# MCU.net
KiCad netlist of a schematic drawn in Altium Designer
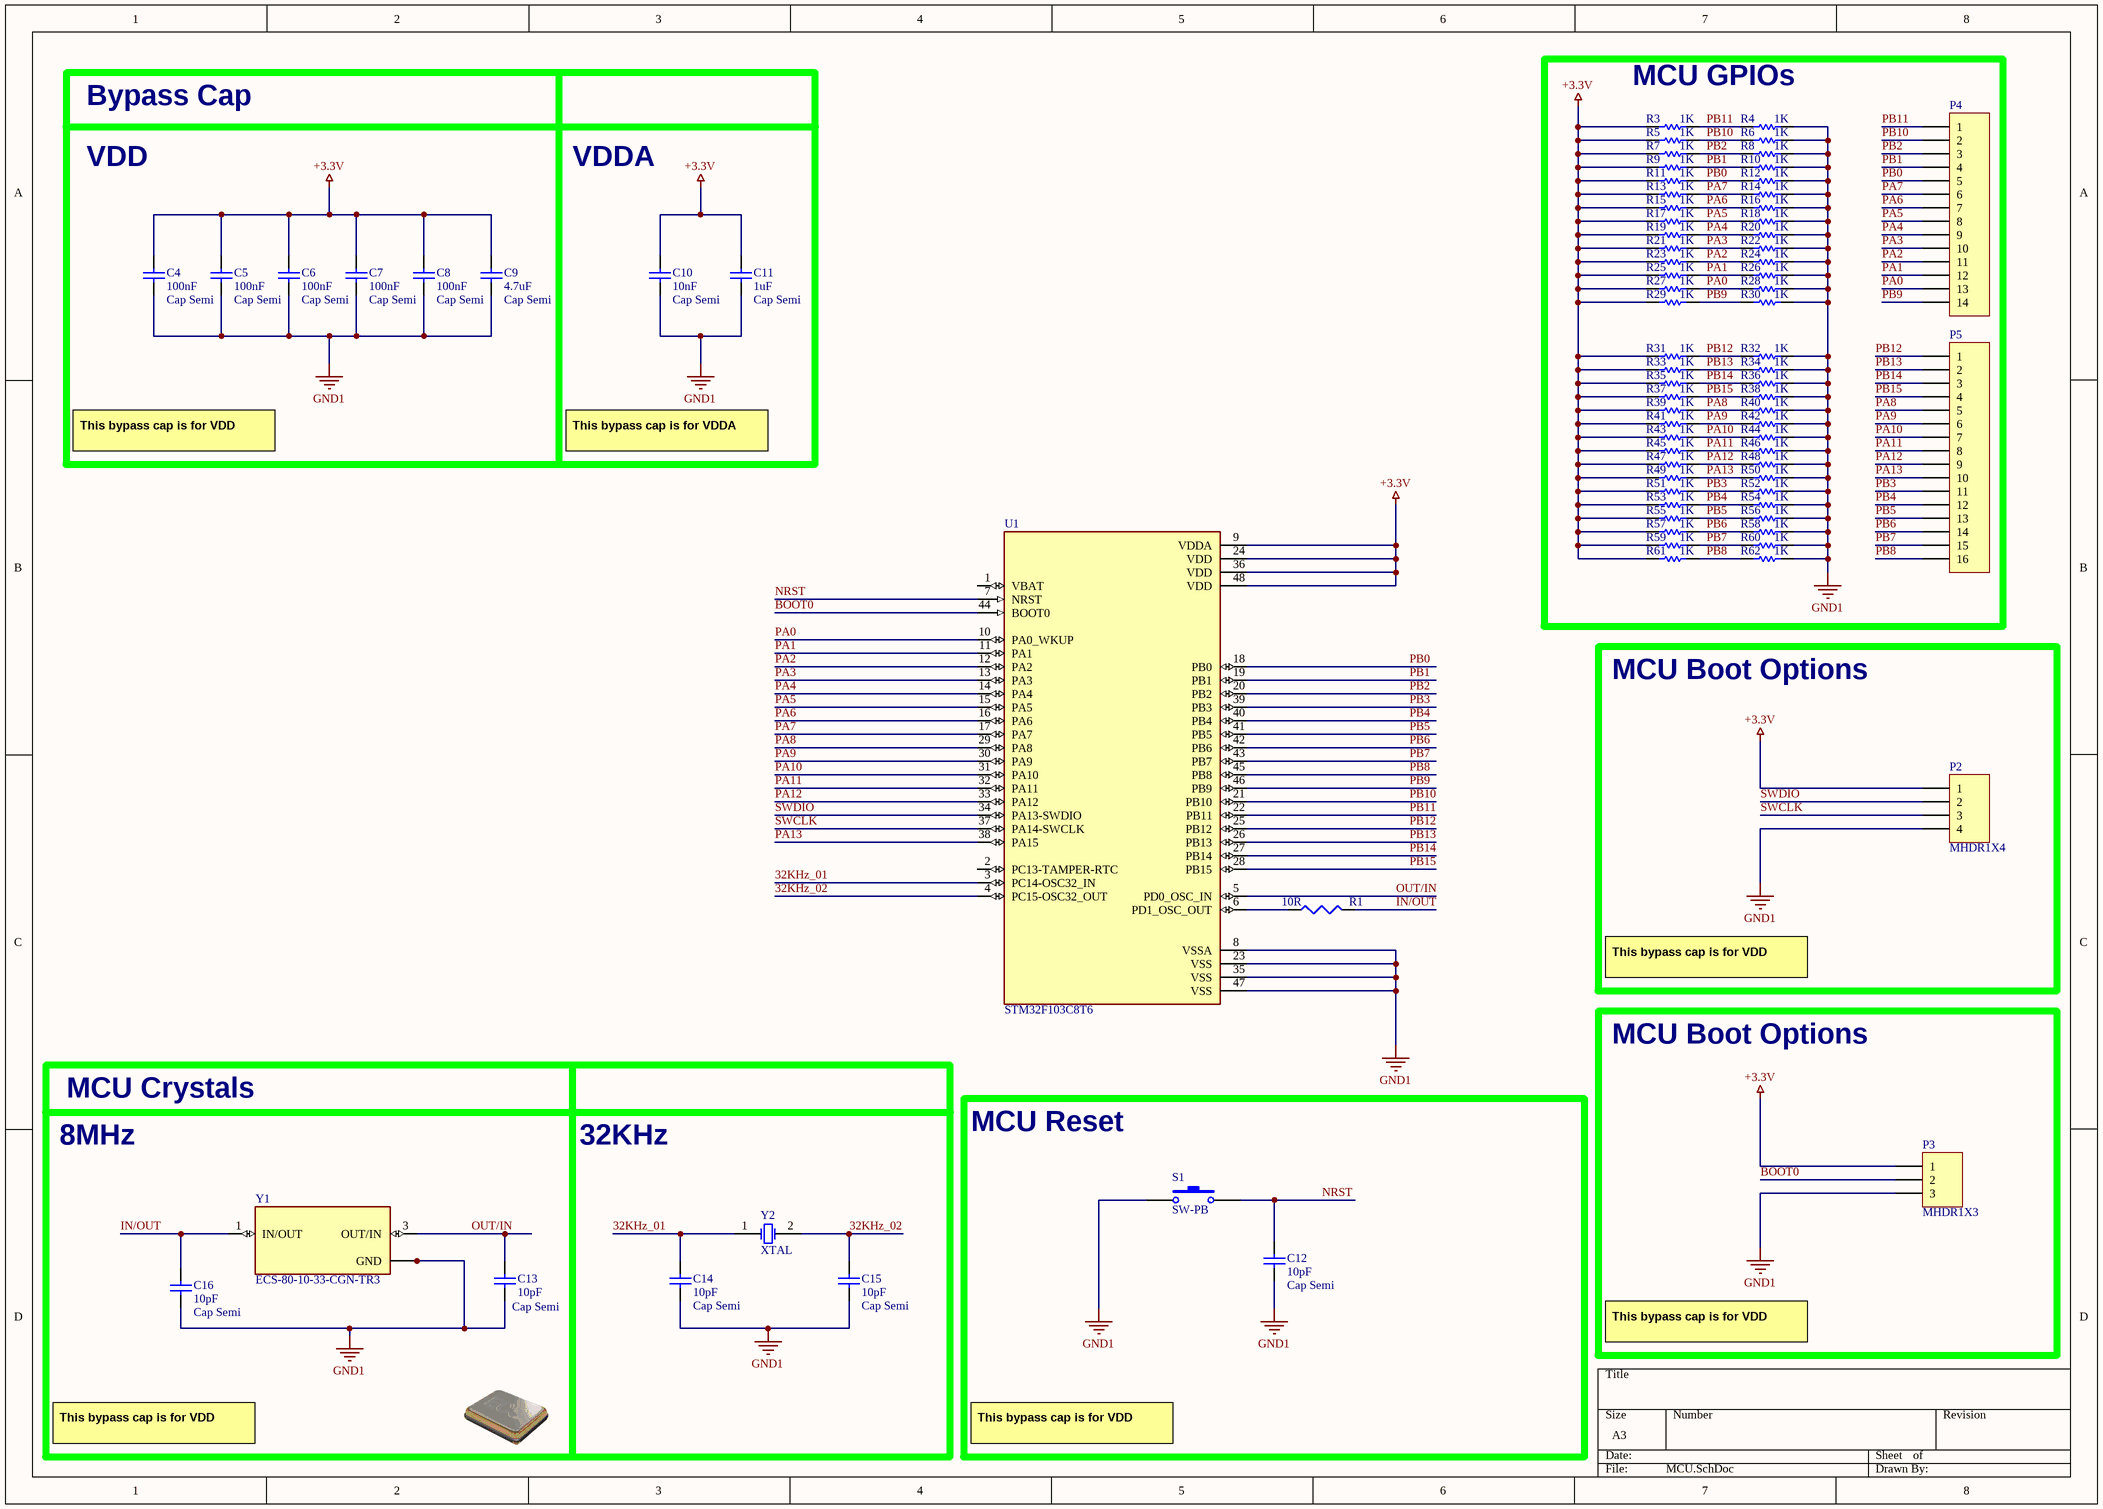
[diagram p0: MCU.SchDoc]

(export (version "E")
  (design (tool "Eeschema 10.0.6"))
  (components
    (comp (ref "C4")
      (value "Cap Semi")
      (footprint "1608[0603]")
      (description "Capacitor (Semiconductor SIM Model)")
      (fields (field (name "ALTIUM_VALUE") "100nF") (field (name "PUBLISHER") "Altium Limited"))
      (libsource (lib "Miscellaneous Devices") (part "Cap Semi"))
    )
    (comp (ref "C5")
      (value "Cap Semi")
      (footprint "1608[0603]")
      (description "Capacitor (Semiconductor SIM Model)")
      (fields (field (name "ALTIUM_VALUE") "100nF") (field (name "PUBLISHER") "Altium Limited"))
      (libsource (lib "Miscellaneous Devices") (part "Cap Semi"))
    )
    (comp (ref "C6")
      (value "Cap Semi")
      (footprint "1608[0603]")
      (description "Capacitor (Semiconductor SIM Model)")
      (fields (field (name "ALTIUM_VALUE") "100nF") (field (name "PUBLISHER") "Altium Limited"))
      (libsource (lib "Miscellaneous Devices") (part "Cap Semi"))
    )
    (comp (ref "C7")
      (value "Cap Semi")
      (footprint "1608[0603]")
      (description "Capacitor (Semiconductor SIM Model)")
      (fields (field (name "ALTIUM_VALUE") "100nF") (field (name "PUBLISHER") "Altium Limited"))
      (libsource (lib "Miscellaneous Devices") (part "Cap Semi"))
    )
    (comp (ref "C8")
      (value "Cap Semi")
      (footprint "1608[0603]")
      (description "Capacitor (Semiconductor SIM Model)")
      (fields (field (name "ALTIUM_VALUE") "100nF") (field (name "PUBLISHER") "Altium Limited"))
      (libsource (lib "Miscellaneous Devices") (part "Cap Semi"))
    )
    (comp (ref "C9")
      (value "Cap Semi")
      (footprint "1608[0603]")
      (description "Capacitor (Semiconductor SIM Model)")
      (fields (field (name "ALTIUM_VALUE") "4.7uF") (field (name "PUBLISHER") "Altium Limited"))
      (libsource (lib "Miscellaneous Devices") (part "Cap Semi"))
    )
    (comp (ref "C10")
      (value "Cap Semi")
      (footprint "1608[0603]")
      (description "Capacitor (Semiconductor SIM Model)")
      (fields (field (name "ALTIUM_VALUE") "10nF") (field (name "PUBLISHER") "Altium Limited"))
      (libsource (lib "Miscellaneous Devices") (part "Cap Semi"))
    )
    (comp (ref "C11")
      (value "Cap Semi")
      (footprint "1608[0603]")
      (description "Capacitor (Semiconductor SIM Model)")
      (fields (field (name "ALTIUM_VALUE") "1uF") (field (name "PUBLISHER") "Altium Limited"))
      (libsource (lib "Miscellaneous Devices") (part "Cap Semi"))
    )
    (comp (ref "C12")
      (value "Cap Semi")
      (footprint "0402")
      (description "Capacitor (Semiconductor SIM Model)")
      (fields (field (name "ALTIUM_VALUE") "10pF") (field (name "PUBLISHER") "Altium Limited"))
      (libsource (lib "Miscellaneous Devices") (part "Cap Semi"))
    )
    (comp (ref "C13")
      (value "Cap Semi")
      (footprint "0402")
      (description "Capacitor (Semiconductor SIM Model)")
      (fields (field (name "ALTIUM_VALUE") "10pF") (field (name "PUBLISHER") "Altium Limited"))
      (libsource (lib "Miscellaneous Devices") (part "Cap Semi"))
    )
    (comp (ref "C14")
      (value "Cap Semi")
      (footprint "0402")
      (description "Capacitor (Semiconductor SIM Model)")
      (fields (field (name "ALTIUM_VALUE") "10pF") (field (name "PUBLISHER") "Altium Limited"))
      (libsource (lib "Miscellaneous Devices") (part "Cap Semi"))
    )
    (comp (ref "C15")
      (value "Cap Semi")
      (footprint "0402")
      (description "Capacitor (Semiconductor SIM Model)")
      (fields (field (name "ALTIUM_VALUE") "10pF") (field (name "PUBLISHER") "Altium Limited"))
      (libsource (lib "Miscellaneous Devices") (part "Cap Semi"))
    )
    (comp (ref "C16")
      (value "Cap Semi")
      (footprint "0402")
      (description "Capacitor (Semiconductor SIM Model)")
      (fields (field (name "ALTIUM_VALUE") "10pF") (field (name "PUBLISHER") "Altium Limited"))
      (libsource (lib "Miscellaneous Devices") (part "Cap Semi"))
    )
    (comp (ref "P2")
      (value "MHDR1X4")
      (footprint "MHDR1X4")
      (description "Header, 4-Pin")
      (fields (field (name "PUBLISHER") "Altium Limited"))
      (libsource (lib "Miscellaneous Connectors") (part "MHDR1X4"))
    )
    (comp (ref "P3")
      (value "MHDR1X3")
      (footprint "MHDR1X3")
      (description "Header, 3-Pin")
      (fields (field (name "PUBLISHER") "Altium Limited"))
      (libsource (lib "Miscellaneous Connectors") (part "MHDR1X3"))
    )
    (comp (ref "P4")
      (value "Header 14")
      (footprint "MY_FE14")
      (description "Header, 14-Pin")
      (fields (field (name "ASID PART NUMBER") "Header 14-AS"))
      (libsource (lib "003 Mylib-Rev-4") (part "Header 14"))
    )
    (comp (ref "P5")
      (value "Header 16")
      (footprint "MY_FE16")
      (description "Header, 16-Pin")
      (fields (field (name "ASID PART NUMBER") "Header 16-AS"))
      (libsource (lib "003 Mylib-Rev-4") (part "Header 16"))
    )
    (comp (ref "R1")
      (value "10R")
      (footprint "J1-0603")
      (description "Resistor")
      (fields (field (name "Comment") "Res3") (field (name "PUBLISHER") "Altium Limited"))
      (libsource (lib "Miscellaneous Devices") (part "Res3"))
    )
    (comp (ref "R3")
      (value "1K")
      (footprint "MY_0603")
      (description "Standard resistor")
      (fields (field (name "ASID PART NUMBER") "Res-AS"))
      (libsource (lib "003 Mylib-Rev-4") (part "Res"))
    )
    (comp (ref "R4")
      (value "1K")
      (footprint "MY_0603")
      (description "Standard resistor")
      (fields (field (name "ASID PART NUMBER") "Res-AS"))
      (libsource (lib "003 Mylib-Rev-4") (part "Res"))
    )
    (comp (ref "R5")
      (value "1K")
      (footprint "MY_0603")
      (description "Standard resistor")
      (fields (field (name "ASID PART NUMBER") "Res-AS"))
      (libsource (lib "003 Mylib-Rev-4") (part "Res"))
    )
    (comp (ref "R6")
      (value "1K")
      (footprint "MY_0603")
      (description "Standard resistor")
      (fields (field (name "ASID PART NUMBER") "Res-AS"))
      (libsource (lib "003 Mylib-Rev-4") (part "Res"))
    )
    (comp (ref "R7")
      (value "1K")
      (footprint "MY_0603")
      (description "Standard resistor")
      (fields (field (name "ASID PART NUMBER") "Res-AS"))
      (libsource (lib "003 Mylib-Rev-4") (part "Res"))
    )
    (comp (ref "R8")
      (value "1K")
      (footprint "MY_0603")
      (description "Standard resistor")
      (fields (field (name "ASID PART NUMBER") "Res-AS"))
      (libsource (lib "003 Mylib-Rev-4") (part "Res"))
    )
    (comp (ref "R9")
      (value "1K")
      (footprint "MY_0603")
      (description "Standard resistor")
      (fields (field (name "ASID PART NUMBER") "Res-AS"))
      (libsource (lib "003 Mylib-Rev-4") (part "Res"))
    )
    (comp (ref "R10")
      (value "1K")
      (footprint "MY_0603")
      (description "Standard resistor")
      (fields (field (name "ASID PART NUMBER") "Res-AS"))
      (libsource (lib "003 Mylib-Rev-4") (part "Res"))
    )
    (comp (ref "R11")
      (value "1K")
      (footprint "MY_0603")
      (description "Standard resistor")
      (fields (field (name "ASID PART NUMBER") "Res-AS"))
      (libsource (lib "003 Mylib-Rev-4") (part "Res"))
    )
    (comp (ref "R12")
      (value "1K")
      (footprint "MY_0603")
      (description "Standard resistor")
      (fields (field (name "ASID PART NUMBER") "Res-AS"))
      (libsource (lib "003 Mylib-Rev-4") (part "Res"))
    )
    (comp (ref "R13")
      (value "1K")
      (footprint "MY_0603")
      (description "Standard resistor")
      (fields (field (name "ASID PART NUMBER") "Res-AS"))
      (libsource (lib "003 Mylib-Rev-4") (part "Res"))
    )
    (comp (ref "R14")
      (value "1K")
      (footprint "MY_0603")
      (description "Standard resistor")
      (fields (field (name "ASID PART NUMBER") "Res-AS"))
      (libsource (lib "003 Mylib-Rev-4") (part "Res"))
    )
    (comp (ref "R15")
      (value "1K")
      (footprint "MY_0603")
      (description "Standard resistor")
      (fields (field (name "ASID PART NUMBER") "Res-AS"))
      (libsource (lib "003 Mylib-Rev-4") (part "Res"))
    )
    (comp (ref "R16")
      (value "1K")
      (footprint "MY_0603")
      (description "Standard resistor")
      (fields (field (name "ASID PART NUMBER") "Res-AS"))
      (libsource (lib "003 Mylib-Rev-4") (part "Res"))
    )
    (comp (ref "R17")
      (value "1K")
      (footprint "MY_0603")
      (description "Standard resistor")
      (fields (field (name "ASID PART NUMBER") "Res-AS"))
      (libsource (lib "003 Mylib-Rev-4") (part "Res"))
    )
    (comp (ref "R18")
      (value "1K")
      (footprint "MY_0603")
      (description "Standard resistor")
      (fields (field (name "ASID PART NUMBER") "Res-AS"))
      (libsource (lib "003 Mylib-Rev-4") (part "Res"))
    )
    (comp (ref "R19")
      (value "1K")
      (footprint "MY_0603")
      (description "Standard resistor")
      (fields (field (name "ASID PART NUMBER") "Res-AS"))
      (libsource (lib "003 Mylib-Rev-4") (part "Res"))
    )
    (comp (ref "R20")
      (value "1K")
      (footprint "MY_0603")
      (description "Standard resistor")
      (fields (field (name "ASID PART NUMBER") "Res-AS"))
      (libsource (lib "003 Mylib-Rev-4") (part "Res"))
    )
    (comp (ref "R21")
      (value "1K")
      (footprint "MY_0603")
      (description "Standard resistor")
      (fields (field (name "ASID PART NUMBER") "Res-AS"))
      (libsource (lib "003 Mylib-Rev-4") (part "Res"))
    )
    (comp (ref "R22")
      (value "1K")
      (footprint "MY_0603")
      (description "Standard resistor")
      (fields (field (name "ASID PART NUMBER") "Res-AS"))
      (libsource (lib "003 Mylib-Rev-4") (part "Res"))
    )
    (comp (ref "R23")
      (value "1K")
      (footprint "MY_0603")
      (description "Standard resistor")
      (fields (field (name "ASID PART NUMBER") "Res-AS"))
      (libsource (lib "003 Mylib-Rev-4") (part "Res"))
    )
    (comp (ref "R24")
      (value "1K")
      (footprint "MY_0603")
      (description "Standard resistor")
      (fields (field (name "ASID PART NUMBER") "Res-AS"))
      (libsource (lib "003 Mylib-Rev-4") (part "Res"))
    )
    (comp (ref "R25")
      (value "1K")
      (footprint "MY_0603")
      (description "Standard resistor")
      (fields (field (name "ASID PART NUMBER") "Res-AS"))
      (libsource (lib "003 Mylib-Rev-4") (part "Res"))
    )
    (comp (ref "R26")
      (value "1K")
      (footprint "MY_0603")
      (description "Standard resistor")
      (fields (field (name "ASID PART NUMBER") "Res-AS"))
      (libsource (lib "003 Mylib-Rev-4") (part "Res"))
    )
    (comp (ref "R27")
      (value "1K")
      (footprint "MY_0603")
      (description "Standard resistor")
      (fields (field (name "ASID PART NUMBER") "Res-AS"))
      (libsource (lib "003 Mylib-Rev-4") (part "Res"))
    )
    (comp (ref "R28")
      (value "1K")
      (footprint "MY_0603")
      (description "Standard resistor")
      (fields (field (name "ASID PART NUMBER") "Res-AS"))
      (libsource (lib "003 Mylib-Rev-4") (part "Res"))
    )
    (comp (ref "R29")
      (value "1K")
      (footprint "MY_0603")
      (description "Standard resistor")
      (fields (field (name "ASID PART NUMBER") "Res-AS"))
      (libsource (lib "003 Mylib-Rev-4") (part "Res"))
    )
    (comp (ref "R30")
      (value "1K")
      (footprint "MY_0603")
      (description "Standard resistor")
      (fields (field (name "ASID PART NUMBER") "Res-AS"))
      (libsource (lib "003 Mylib-Rev-4") (part "Res"))
    )
    (comp (ref "R31")
      (value "1K")
      (footprint "MY_0603")
      (description "Standard resistor")
      (fields (field (name "ASID PART NUMBER") "Res-AS"))
      (libsource (lib "003 Mylib-Rev-4") (part "Res"))
    )
    (comp (ref "R32")
      (value "1K")
      (footprint "MY_0603")
      (description "Standard resistor")
      (fields (field (name "ASID PART NUMBER") "Res-AS"))
      (libsource (lib "003 Mylib-Rev-4") (part "Res"))
    )
    (comp (ref "R33")
      (value "1K")
      (footprint "MY_0603")
      (description "Standard resistor")
      (fields (field (name "ASID PART NUMBER") "Res-AS"))
      (libsource (lib "003 Mylib-Rev-4") (part "Res"))
    )
    (comp (ref "R34")
      (value "1K")
      (footprint "MY_0603")
      (description "Standard resistor")
      (fields (field (name "ASID PART NUMBER") "Res-AS"))
      (libsource (lib "003 Mylib-Rev-4") (part "Res"))
    )
    (comp (ref "R35")
      (value "1K")
      (footprint "MY_0603")
      (description "Standard resistor")
      (fields (field (name "ASID PART NUMBER") "Res-AS"))
      (libsource (lib "003 Mylib-Rev-4") (part "Res"))
    )
    (comp (ref "R36")
      (value "1K")
      (footprint "MY_0603")
      (description "Standard resistor")
      (fields (field (name "ASID PART NUMBER") "Res-AS"))
      (libsource (lib "003 Mylib-Rev-4") (part "Res"))
    )
    (comp (ref "R37")
      (value "1K")
      (footprint "MY_0603")
      (description "Standard resistor")
      (fields (field (name "ASID PART NUMBER") "Res-AS"))
      (libsource (lib "003 Mylib-Rev-4") (part "Res"))
    )
    (comp (ref "R38")
      (value "1K")
      (footprint "MY_0603")
      (description "Standard resistor")
      (fields (field (name "ASID PART NUMBER") "Res-AS"))
      (libsource (lib "003 Mylib-Rev-4") (part "Res"))
    )
    (comp (ref "R39")
      (value "1K")
      (footprint "MY_0603")
      (description "Standard resistor")
      (fields (field (name "ASID PART NUMBER") "Res-AS"))
      (libsource (lib "003 Mylib-Rev-4") (part "Res"))
    )
    (comp (ref "R40")
      (value "1K")
      (footprint "MY_0603")
      (description "Standard resistor")
      (fields (field (name "ASID PART NUMBER") "Res-AS"))
      (libsource (lib "003 Mylib-Rev-4") (part "Res"))
    )
    (comp (ref "R41")
      (value "1K")
      (footprint "MY_0603")
      (description "Standard resistor")
      (fields (field (name "ASID PART NUMBER") "Res-AS"))
      (libsource (lib "003 Mylib-Rev-4") (part "Res"))
    )
    (comp (ref "R42")
      (value "1K")
      (footprint "MY_0603")
      (description "Standard resistor")
      (fields (field (name "ASID PART NUMBER") "Res-AS"))
      (libsource (lib "003 Mylib-Rev-4") (part "Res"))
    )
    (comp (ref "R43")
      (value "1K")
      (footprint "MY_0603")
      (description "Standard resistor")
      (fields (field (name "ASID PART NUMBER") "Res-AS"))
      (libsource (lib "003 Mylib-Rev-4") (part "Res"))
    )
    (comp (ref "R44")
      (value "1K")
      (footprint "MY_0603")
      (description "Standard resistor")
      (fields (field (name "ASID PART NUMBER") "Res-AS"))
      (libsource (lib "003 Mylib-Rev-4") (part "Res"))
    )
    (comp (ref "R45")
      (value "1K")
      (footprint "MY_0603")
      (description "Standard resistor")
      (fields (field (name "ASID PART NUMBER") "Res-AS"))
      (libsource (lib "003 Mylib-Rev-4") (part "Res"))
    )
    (comp (ref "R46")
      (value "1K")
      (footprint "MY_0603")
      (description "Standard resistor")
      (fields (field (name "ASID PART NUMBER") "Res-AS"))
      (libsource (lib "003 Mylib-Rev-4") (part "Res"))
    )
    (comp (ref "R47")
      (value "1K")
      (footprint "MY_0603")
      (description "Standard resistor")
      (fields (field (name "ASID PART NUMBER") "Res-AS"))
      (libsource (lib "003 Mylib-Rev-4") (part "Res"))
    )
    (comp (ref "R48")
      (value "1K")
      (footprint "MY_0603")
      (description "Standard resistor")
      (fields (field (name "ASID PART NUMBER") "Res-AS"))
      (libsource (lib "003 Mylib-Rev-4") (part "Res"))
    )
    (comp (ref "R49")
      (value "1K")
      (footprint "MY_0603")
      (description "Standard resistor")
      (fields (field (name "ASID PART NUMBER") "Res-AS"))
      (libsource (lib "003 Mylib-Rev-4") (part "Res"))
    )
    (comp (ref "R50")
      (value "1K")
      (footprint "MY_0603")
      (description "Standard resistor")
      (fields (field (name "ASID PART NUMBER") "Res-AS"))
      (libsource (lib "003 Mylib-Rev-4") (part "Res"))
    )
    (comp (ref "R51")
      (value "1K")
      (footprint "MY_0603")
      (description "Standard resistor")
      (fields (field (name "ASID PART NUMBER") "Res-AS"))
      (libsource (lib "003 Mylib-Rev-4") (part "Res"))
    )
    (comp (ref "R52")
      (value "1K")
      (footprint "MY_0603")
      (description "Standard resistor")
      (fields (field (name "ASID PART NUMBER") "Res-AS"))
      (libsource (lib "003 Mylib-Rev-4") (part "Res"))
    )
    (comp (ref "R53")
      (value "1K")
      (footprint "MY_0603")
      (description "Standard resistor")
      (fields (field (name "ASID PART NUMBER") "Res-AS"))
      (libsource (lib "003 Mylib-Rev-4") (part "Res"))
    )
    (comp (ref "R54")
      (value "1K")
      (footprint "MY_0603")
      (description "Standard resistor")
      (fields (field (name "ASID PART NUMBER") "Res-AS"))
      (libsource (lib "003 Mylib-Rev-4") (part "Res"))
    )
    (comp (ref "R55")
      (value "1K")
      (footprint "MY_0603")
      (description "Standard resistor")
      (fields (field (name "ASID PART NUMBER") "Res-AS"))
      (libsource (lib "003 Mylib-Rev-4") (part "Res"))
    )
    (comp (ref "R56")
      (value "1K")
      (footprint "MY_0603")
      (description "Standard resistor")
      (fields (field (name "ASID PART NUMBER") "Res-AS"))
      (libsource (lib "003 Mylib-Rev-4") (part "Res"))
    )
    (comp (ref "R57")
      (value "1K")
      (footprint "MY_0603")
      (description "Standard resistor")
      (fields (field (name "ASID PART NUMBER") "Res-AS"))
      (libsource (lib "003 Mylib-Rev-4") (part "Res"))
    )
    (comp (ref "R58")
      (value "1K")
      (footprint "MY_0603")
      (description "Standard resistor")
      (fields (field (name "ASID PART NUMBER") "Res-AS"))
      (libsource (lib "003 Mylib-Rev-4") (part "Res"))
    )
    (comp (ref "R59")
      (value "1K")
      (footprint "MY_0603")
      (description "Standard resistor")
      (fields (field (name "ASID PART NUMBER") "Res-AS"))
      (libsource (lib "003 Mylib-Rev-4") (part "Res"))
    )
    (comp (ref "R60")
      (value "1K")
      (footprint "MY_0603")
      (description "Standard resistor")
      (fields (field (name "ASID PART NUMBER") "Res-AS"))
      (libsource (lib "003 Mylib-Rev-4") (part "Res"))
    )
    (comp (ref "R61")
      (value "1K")
      (footprint "MY_0603")
      (description "Standard resistor")
      (fields (field (name "ASID PART NUMBER") "Res-AS"))
      (libsource (lib "003 Mylib-Rev-4") (part "Res"))
    )
    (comp (ref "R62")
      (value "1K")
      (footprint "MY_0603")
      (description "Standard resistor")
      (fields (field (name "ASID PART NUMBER") "Res-AS"))
      (libsource (lib "003 Mylib-Rev-4") (part "Res"))
    )
    (comp (ref "S1")
      (value "SW-PB")
      (footprint "SPST-2")
      (description "Switch")
      (fields (field (name "PUBLISHER") "Altium Limited"))
      (libsource (lib "Miscellaneous Devices") (part "SW-PB"))
    )
    (comp (ref "U1")
      (value "STM32F103C8T6")
      (footprint "QFP50P900X900X160-48N")
      (description "ARM® Cortex®-M3 STM32F1 Microcontroller IC 32-Bit 72MHz 64KB (64K x 8) FLASH 48-LQFP (7x7)")
      (fields (field (name "MF") "STMicroelectronics"))
      (libsource (lib "STM32F103C8T6") (part "STM32F103C8T6"))
    )
    (comp (ref "Y1")
      (value "ECS-80-10-33-CGN-TR3")
      (footprint "XTAL_ECS-80-10-33-CGN-TR3")
      (libsource (lib "ECS-80-10-33-CGN-TR3") (part "ECS-80-10-33-CGN-TR3"))
    )
    (comp (ref "Y2")
      (value "XTAL")
      (footprint "R38")
      (description "Crystal Oscillator")
      (fields (field (name "PUBLISHER") "Altium Limited"))
      (libsource (lib "Miscellaneous Devices") (part "XTAL"))
    )
  )
  (nets
    (net (code "1") (name "+3.3V") (class "Default")
      (node (ref "C10") (pin "2") (pinfunction "2_2") (pintype "passive"))
      (node (ref "C11") (pin "2") (pinfunction "2_2") (pintype "passive"))
      (node (ref "C4") (pin "2") (pinfunction "2_2") (pintype "passive"))
      (node (ref "C5") (pin "2") (pinfunction "2_2") (pintype "passive"))
      (node (ref "C6") (pin "2") (pinfunction "2_2") (pintype "passive"))
      (node (ref "C7") (pin "2") (pinfunction "2_2") (pintype "passive"))
      (node (ref "C8") (pin "2") (pinfunction "2_2") (pintype "passive"))
      (node (ref "C9") (pin "2") (pinfunction "2_2") (pintype "passive"))
      (node (ref "P2") (pin "1") (pinfunction "1_1") (pintype "passive"))
      (node (ref "P3") (pin "1") (pinfunction "1_1") (pintype "passive"))
      (node (ref "R11") (pin "1") (pinfunction "1_1") (pintype "passive"))
      (node (ref "R13") (pin "1") (pinfunction "1_1") (pintype "passive"))
      (node (ref "R15") (pin "1") (pinfunction "1_1") (pintype "passive"))
      (node (ref "R17") (pin "1") (pinfunction "1_1") (pintype "passive"))
      (node (ref "R19") (pin "1") (pinfunction "1_1") (pintype "passive"))
      (node (ref "R21") (pin "1") (pinfunction "1_1") (pintype "passive"))
      (node (ref "R23") (pin "1") (pinfunction "1_1") (pintype "passive"))
      (node (ref "R25") (pin "1") (pinfunction "1_1") (pintype "passive"))
      (node (ref "R27") (pin "1") (pinfunction "1_1") (pintype "passive"))
      (node (ref "R29") (pin "1") (pinfunction "1_1") (pintype "passive"))
      (node (ref "R3") (pin "1") (pinfunction "1_1") (pintype "passive"))
      (node (ref "R31") (pin "1") (pinfunction "1_1") (pintype "passive"))
      (node (ref "R33") (pin "1") (pinfunction "1_1") (pintype "passive"))
      (node (ref "R35") (pin "1") (pinfunction "1_1") (pintype "passive"))
      (node (ref "R37") (pin "1") (pinfunction "1_1") (pintype "passive"))
      (node (ref "R39") (pin "1") (pinfunction "1_1") (pintype "passive"))
      (node (ref "R41") (pin "1") (pinfunction "1_1") (pintype "passive"))
      (node (ref "R43") (pin "1") (pinfunction "1_1") (pintype "passive"))
      (node (ref "R45") (pin "1") (pinfunction "1_1") (pintype "passive"))
      (node (ref "R47") (pin "1") (pinfunction "1_1") (pintype "passive"))
      (node (ref "R49") (pin "1") (pinfunction "1_1") (pintype "passive"))
      (node (ref "R5") (pin "1") (pinfunction "1_1") (pintype "passive"))
      (node (ref "R51") (pin "1") (pinfunction "1_1") (pintype "passive"))
      (node (ref "R53") (pin "1") (pinfunction "1_1") (pintype "passive"))
      (node (ref "R55") (pin "1") (pinfunction "1_1") (pintype "passive"))
      (node (ref "R57") (pin "1") (pinfunction "1_1") (pintype "passive"))
      (node (ref "R59") (pin "1") (pinfunction "1_1") (pintype "passive"))
      (node (ref "R61") (pin "1") (pinfunction "1_1") (pintype "passive"))
      (node (ref "R7") (pin "1") (pinfunction "1_1") (pintype "passive"))
      (node (ref "R9") (pin "1") (pinfunction "1_1") (pintype "passive"))
      (node (ref "U1") (pin "24") (pinfunction "VDD_24") (pintype "power_in"))
      (node (ref "U1") (pin "36") (pinfunction "VDD_36") (pintype "power_in"))
      (node (ref "U1") (pin "48") (pinfunction "VDD_48") (pintype "power_in"))
      (node (ref "U1") (pin "9") (pinfunction "VDDA_9") (pintype "power_in"))
    )
    (net (code "2") (name "/32KHz_01") (class "Default")
      (node (ref "C14") (pin "2") (pinfunction "2_2") (pintype "passive"))
      (node (ref "U1") (pin "3") (pinfunction "PC14-OSC32_IN_3") (pintype "bidirectional"))
      (node (ref "Y2") (pin "1") (pinfunction "OSC1_1") (pintype "passive"))
    )
    (net (code "3") (name "/32KHz_02") (class "Default")
      (node (ref "C15") (pin "2") (pinfunction "2_2") (pintype "passive"))
      (node (ref "U1") (pin "4") (pinfunction "PC15-OSC32_OUT_4") (pintype "bidirectional"))
      (node (ref "Y2") (pin "2") (pinfunction "OSC2_2") (pintype "passive"))
    )
    (net (code "4") (name "/BOOT0") (class "Default")
      (node (ref "P3") (pin "2") (pinfunction "2_2") (pintype "passive"))
      (node (ref "U1") (pin "44") (pinfunction "BOOT0_44") (pintype "input"))
    )
    (net (code "5") (name "/IN{slash}OUT") (class "Default")
      (node (ref "C16") (pin "2") (pinfunction "2_2") (pintype "passive"))
      (node (ref "R1") (pin "2") (pinfunction "2_2") (pintype "passive"))
      (node (ref "Y1") (pin "1") (pinfunction "IN/OUT_1") (pintype "bidirectional"))
    )
    (net (code "6") (name "/NRST") (class "Default")
      (node (ref "C12") (pin "2") (pinfunction "2_2") (pintype "passive"))
      (node (ref "S1") (pin "2") (pinfunction "2_2") (pintype "passive"))
      (node (ref "U1") (pin "7") (pinfunction "NRST_7") (pintype "input"))
    )
    (net (code "7") (name "/OUT{slash}IN") (class "Default")
      (node (ref "C13") (pin "2") (pinfunction "2_2") (pintype "passive"))
      (node (ref "U1") (pin "5") (pinfunction "PD0_OSC_IN_5") (pintype "bidirectional"))
      (node (ref "Y1") (pin "3") (pinfunction "OUT/IN_3") (pintype "bidirectional"))
    )
    (net (code "8") (name "/PA0") (class "Default")
      (node (ref "P4") (pin "13") (pinfunction "13_13") (pintype "passive"))
      (node (ref "R27") (pin "2") (pinfunction "2_2") (pintype "passive"))
      (node (ref "R28") (pin "1") (pinfunction "1_1") (pintype "passive"))
      (node (ref "U1") (pin "10") (pinfunction "PA0_WKUP_10") (pintype "bidirectional"))
    )
    (net (code "9") (name "/PA1") (class "Default")
      (node (ref "P4") (pin "12") (pinfunction "12_12") (pintype "passive"))
      (node (ref "R25") (pin "2") (pinfunction "2_2") (pintype "passive"))
      (node (ref "R26") (pin "1") (pinfunction "1_1") (pintype "passive"))
      (node (ref "U1") (pin "11") (pinfunction "PA1_11") (pintype "bidirectional"))
    )
    (net (code "10") (name "/PA2") (class "Default")
      (node (ref "P4") (pin "11") (pinfunction "11_11") (pintype "passive"))
      (node (ref "R23") (pin "2") (pinfunction "2_2") (pintype "passive"))
      (node (ref "R24") (pin "1") (pinfunction "1_1") (pintype "passive"))
      (node (ref "U1") (pin "12") (pinfunction "PA2_12") (pintype "bidirectional"))
    )
    (net (code "11") (name "/PA3") (class "Default")
      (node (ref "P4") (pin "10") (pinfunction "10_10") (pintype "passive"))
      (node (ref "R21") (pin "2") (pinfunction "2_2") (pintype "passive"))
      (node (ref "R22") (pin "1") (pinfunction "1_1") (pintype "passive"))
      (node (ref "U1") (pin "13") (pinfunction "PA3_13") (pintype "bidirectional"))
    )
    (net (code "12") (name "/PA4") (class "Default")
      (node (ref "P4") (pin "9") (pinfunction "9_9") (pintype "passive"))
      (node (ref "R19") (pin "2") (pinfunction "2_2") (pintype "passive"))
      (node (ref "R20") (pin "1") (pinfunction "1_1") (pintype "passive"))
      (node (ref "U1") (pin "14") (pinfunction "PA4_14") (pintype "bidirectional"))
    )
    (net (code "13") (name "/PA5") (class "Default")
      (node (ref "P4") (pin "8") (pinfunction "8_8") (pintype "passive"))
      (node (ref "R17") (pin "2") (pinfunction "2_2") (pintype "passive"))
      (node (ref "R18") (pin "1") (pinfunction "1_1") (pintype "passive"))
      (node (ref "U1") (pin "15") (pinfunction "PA5_15") (pintype "bidirectional"))
    )
    (net (code "14") (name "/PA6") (class "Default")
      (node (ref "P4") (pin "7") (pinfunction "7_7") (pintype "passive"))
      (node (ref "R15") (pin "2") (pinfunction "2_2") (pintype "passive"))
      (node (ref "R16") (pin "1") (pinfunction "1_1") (pintype "passive"))
      (node (ref "U1") (pin "16") (pinfunction "PA6_16") (pintype "bidirectional"))
    )
    (net (code "15") (name "/PA7") (class "Default")
      (node (ref "P4") (pin "6") (pinfunction "6_6") (pintype "passive"))
      (node (ref "R13") (pin "2") (pinfunction "2_2") (pintype "passive"))
      (node (ref "R14") (pin "1") (pinfunction "1_1") (pintype "passive"))
      (node (ref "U1") (pin "17") (pinfunction "PA7_17") (pintype "bidirectional"))
    )
    (net (code "16") (name "/PA8") (class "Default")
      (node (ref "P5") (pin "5") (pinfunction "5_5") (pintype "passive"))
      (node (ref "R39") (pin "2") (pinfunction "2_2") (pintype "passive"))
      (node (ref "R40") (pin "1") (pinfunction "1_1") (pintype "passive"))
      (node (ref "U1") (pin "29") (pinfunction "PA8_29") (pintype "bidirectional"))
    )
    (net (code "17") (name "/PA9") (class "Default")
      (node (ref "P5") (pin "6") (pinfunction "6_6") (pintype "passive"))
      (node (ref "R41") (pin "2") (pinfunction "2_2") (pintype "passive"))
      (node (ref "R42") (pin "1") (pinfunction "1_1") (pintype "passive"))
      (node (ref "U1") (pin "30") (pinfunction "PA9_30") (pintype "bidirectional"))
    )
    (net (code "18") (name "/PA10") (class "Default")
      (node (ref "P5") (pin "7") (pinfunction "7_7") (pintype "passive"))
      (node (ref "R43") (pin "2") (pinfunction "2_2") (pintype "passive"))
      (node (ref "R44") (pin "1") (pinfunction "1_1") (pintype "passive"))
      (node (ref "U1") (pin "31") (pinfunction "PA10_31") (pintype "bidirectional"))
    )
    (net (code "19") (name "/PA11") (class "Default")
      (node (ref "P5") (pin "8") (pinfunction "8_8") (pintype "passive"))
      (node (ref "R45") (pin "2") (pinfunction "2_2") (pintype "passive"))
      (node (ref "R46") (pin "1") (pinfunction "1_1") (pintype "passive"))
      (node (ref "U1") (pin "32") (pinfunction "PA11_32") (pintype "bidirectional"))
    )
    (net (code "20") (name "/PA12") (class "Default")
      (node (ref "P5") (pin "9") (pinfunction "9_9") (pintype "passive"))
      (node (ref "R47") (pin "2") (pinfunction "2_2") (pintype "passive"))
      (node (ref "R48") (pin "1") (pinfunction "1_1") (pintype "passive"))
      (node (ref "U1") (pin "33") (pinfunction "PA12_33") (pintype "bidirectional"))
    )
    (net (code "21") (name "/PA13") (class "Default")
      (node (ref "P5") (pin "10") (pinfunction "10_10") (pintype "passive"))
      (node (ref "R49") (pin "2") (pinfunction "2_2") (pintype "passive"))
      (node (ref "R50") (pin "1") (pinfunction "1_1") (pintype "passive"))
      (node (ref "U1") (pin "38") (pinfunction "PA15_38") (pintype "bidirectional"))
    )
    (net (code "22") (name "/PB0") (class "Default")
      (node (ref "P4") (pin "5") (pinfunction "5_5") (pintype "passive"))
      (node (ref "R11") (pin "2") (pinfunction "2_2") (pintype "passive"))
      (node (ref "R12") (pin "1") (pinfunction "1_1") (pintype "passive"))
      (node (ref "U1") (pin "18") (pinfunction "PB0_18") (pintype "bidirectional"))
    )
    (net (code "23") (name "/PB1") (class "Default")
      (node (ref "P4") (pin "4") (pinfunction "4_4") (pintype "passive"))
      (node (ref "R10") (pin "1") (pinfunction "1_1") (pintype "passive"))
      (node (ref "R9") (pin "2") (pinfunction "2_2") (pintype "passive"))
      (node (ref "U1") (pin "19") (pinfunction "PB1_19") (pintype "bidirectional"))
    )
    (net (code "24") (name "/PB2") (class "Default")
      (node (ref "P4") (pin "3") (pinfunction "3_3") (pintype "passive"))
      (node (ref "R7") (pin "2") (pinfunction "2_2") (pintype "passive"))
      (node (ref "R8") (pin "1") (pinfunction "1_1") (pintype "passive"))
      (node (ref "U1") (pin "20") (pinfunction "PB2_20") (pintype "bidirectional"))
    )
    (net (code "25") (name "/PB3") (class "Default")
      (node (ref "P5") (pin "11") (pinfunction "11_11") (pintype "passive"))
      (node (ref "R51") (pin "2") (pinfunction "2_2") (pintype "passive"))
      (node (ref "R52") (pin "1") (pinfunction "1_1") (pintype "passive"))
      (node (ref "U1") (pin "39") (pinfunction "PB3_39") (pintype "bidirectional"))
    )
    (net (code "26") (name "/PB4") (class "Default")
      (node (ref "P5") (pin "12") (pinfunction "12_12") (pintype "passive"))
      (node (ref "R53") (pin "2") (pinfunction "2_2") (pintype "passive"))
      (node (ref "R54") (pin "1") (pinfunction "1_1") (pintype "passive"))
      (node (ref "U1") (pin "40") (pinfunction "PB4_40") (pintype "bidirectional"))
    )
    (net (code "27") (name "/PB5") (class "Default")
      (node (ref "P5") (pin "13") (pinfunction "13_13") (pintype "passive"))
      (node (ref "R55") (pin "2") (pinfunction "2_2") (pintype "passive"))
      (node (ref "R56") (pin "1") (pinfunction "1_1") (pintype "passive"))
      (node (ref "U1") (pin "41") (pinfunction "PB5_41") (pintype "bidirectional"))
    )
    (net (code "28") (name "/PB6") (class "Default")
      (node (ref "P5") (pin "14") (pinfunction "14_14") (pintype "passive"))
      (node (ref "R57") (pin "2") (pinfunction "2_2") (pintype "passive"))
      (node (ref "R58") (pin "1") (pinfunction "1_1") (pintype "passive"))
      (node (ref "U1") (pin "42") (pinfunction "PB6_42") (pintype "bidirectional"))
    )
    (net (code "29") (name "/PB7") (class "Default")
      (node (ref "P5") (pin "15") (pinfunction "15_15") (pintype "passive"))
      (node (ref "R59") (pin "2") (pinfunction "2_2") (pintype "passive"))
      (node (ref "R60") (pin "1") (pinfunction "1_1") (pintype "passive"))
      (node (ref "U1") (pin "43") (pinfunction "PB7_43") (pintype "bidirectional"))
    )
    (net (code "30") (name "/PB8") (class "Default")
      (node (ref "P5") (pin "16") (pinfunction "16_16") (pintype "passive"))
      (node (ref "R61") (pin "2") (pinfunction "2_2") (pintype "passive"))
      (node (ref "R62") (pin "1") (pinfunction "1_1") (pintype "passive"))
      (node (ref "U1") (pin "45") (pinfunction "PB8_45") (pintype "bidirectional"))
    )
    (net (code "31") (name "/PB9") (class "Default")
      (node (ref "P4") (pin "14") (pinfunction "14_14") (pintype "passive"))
      (node (ref "R29") (pin "2") (pinfunction "2_2") (pintype "passive"))
      (node (ref "R30") (pin "1") (pinfunction "1_1") (pintype "passive"))
      (node (ref "U1") (pin "46") (pinfunction "PB9_46") (pintype "bidirectional"))
    )
    (net (code "32") (name "/PB10") (class "Default")
      (node (ref "P4") (pin "2") (pinfunction "2_2") (pintype "passive"))
      (node (ref "R5") (pin "2") (pinfunction "2_2") (pintype "passive"))
      (node (ref "R6") (pin "1") (pinfunction "1_1") (pintype "passive"))
      (node (ref "U1") (pin "21") (pinfunction "PB10_21") (pintype "bidirectional"))
    )
    (net (code "33") (name "/PB11") (class "Default")
      (node (ref "P4") (pin "1") (pinfunction "1_1") (pintype "passive"))
      (node (ref "R3") (pin "2") (pinfunction "2_2") (pintype "passive"))
      (node (ref "R4") (pin "1") (pinfunction "1_1") (pintype "passive"))
      (node (ref "U1") (pin "22") (pinfunction "PB11_22") (pintype "bidirectional"))
    )
    (net (code "34") (name "/PB12") (class "Default")
      (node (ref "P5") (pin "1") (pinfunction "1_1") (pintype "passive"))
      (node (ref "R31") (pin "2") (pinfunction "2_2") (pintype "passive"))
      (node (ref "R32") (pin "1") (pinfunction "1_1") (pintype "passive"))
      (node (ref "U1") (pin "25") (pinfunction "PB12_25") (pintype "bidirectional"))
    )
    (net (code "35") (name "/PB13") (class "Default")
      (node (ref "P5") (pin "2") (pinfunction "2_2") (pintype "passive"))
      (node (ref "R33") (pin "2") (pinfunction "2_2") (pintype "passive"))
      (node (ref "R34") (pin "1") (pinfunction "1_1") (pintype "passive"))
      (node (ref "U1") (pin "26") (pinfunction "PB13_26") (pintype "bidirectional"))
    )
    (net (code "36") (name "/PB14") (class "Default")
      (node (ref "P5") (pin "3") (pinfunction "3_3") (pintype "passive"))
      (node (ref "R35") (pin "2") (pinfunction "2_2") (pintype "passive"))
      (node (ref "R36") (pin "1") (pinfunction "1_1") (pintype "passive"))
      (node (ref "U1") (pin "27") (pinfunction "PB14_27") (pintype "bidirectional"))
    )
    (net (code "37") (name "/PB15") (class "Default")
      (node (ref "P5") (pin "4") (pinfunction "4_4") (pintype "passive"))
      (node (ref "R37") (pin "2") (pinfunction "2_2") (pintype "passive"))
      (node (ref "R38") (pin "1") (pinfunction "1_1") (pintype "passive"))
      (node (ref "U1") (pin "28") (pinfunction "PB15_28") (pintype "bidirectional"))
    )
    (net (code "38") (name "/SWCLK") (class "Default")
      (node (ref "P2") (pin "3") (pinfunction "3_3") (pintype "passive"))
      (node (ref "U1") (pin "37") (pinfunction "PA14-SWCLK_37") (pintype "bidirectional"))
    )
    (net (code "39") (name "/SWDIO") (class "Default")
      (node (ref "P2") (pin "2") (pinfunction "2_2") (pintype "passive"))
      (node (ref "U1") (pin "34") (pinfunction "PA13-SWDIO_34") (pintype "bidirectional"))
    )
    (net (code "40") (name "GND1") (class "Default")
      (node (ref "C10") (pin "1") (pinfunction "1_1") (pintype "passive"))
      (node (ref "C11") (pin "1") (pinfunction "1_1") (pintype "passive"))
      (node (ref "C12") (pin "1") (pinfunction "1_1") (pintype "passive"))
      (node (ref "C13") (pin "1") (pinfunction "1_1") (pintype "passive"))
      (node (ref "C14") (pin "1") (pinfunction "1_1") (pintype "passive"))
      (node (ref "C15") (pin "1") (pinfunction "1_1") (pintype "passive"))
      (node (ref "C16") (pin "1") (pinfunction "1_1") (pintype "passive"))
      (node (ref "C4") (pin "1") (pinfunction "1_1") (pintype "passive"))
      (node (ref "C5") (pin "1") (pinfunction "1_1") (pintype "passive"))
      (node (ref "C6") (pin "1") (pinfunction "1_1") (pintype "passive"))
      (node (ref "C7") (pin "1") (pinfunction "1_1") (pintype "passive"))
      (node (ref "C8") (pin "1") (pinfunction "1_1") (pintype "passive"))
      (node (ref "C9") (pin "1") (pinfunction "1_1") (pintype "passive"))
      (node (ref "P2") (pin "4") (pinfunction "4_4") (pintype "passive"))
      (node (ref "P3") (pin "3") (pinfunction "3_3") (pintype "passive"))
      (node (ref "R10") (pin "2") (pinfunction "2_2") (pintype "passive"))
      (node (ref "R12") (pin "2") (pinfunction "2_2") (pintype "passive"))
      (node (ref "R14") (pin "2") (pinfunction "2_2") (pintype "passive"))
      (node (ref "R16") (pin "2") (pinfunction "2_2") (pintype "passive"))
      (node (ref "R18") (pin "2") (pinfunction "2_2") (pintype "passive"))
      (node (ref "R20") (pin "2") (pinfunction "2_2") (pintype "passive"))
      (node (ref "R22") (pin "2") (pinfunction "2_2") (pintype "passive"))
      (node (ref "R24") (pin "2") (pinfunction "2_2") (pintype "passive"))
      (node (ref "R26") (pin "2") (pinfunction "2_2") (pintype "passive"))
      (node (ref "R28") (pin "2") (pinfunction "2_2") (pintype "passive"))
      (node (ref "R30") (pin "2") (pinfunction "2_2") (pintype "passive"))
      (node (ref "R32") (pin "2") (pinfunction "2_2") (pintype "passive"))
      (node (ref "R34") (pin "2") (pinfunction "2_2") (pintype "passive"))
      (node (ref "R36") (pin "2") (pinfunction "2_2") (pintype "passive"))
      (node (ref "R38") (pin "2") (pinfunction "2_2") (pintype "passive"))
      (node (ref "R4") (pin "2") (pinfunction "2_2") (pintype "passive"))
      (node (ref "R40") (pin "2") (pinfunction "2_2") (pintype "passive"))
      (node (ref "R42") (pin "2") (pinfunction "2_2") (pintype "passive"))
      (node (ref "R44") (pin "2") (pinfunction "2_2") (pintype "passive"))
      (node (ref "R46") (pin "2") (pinfunction "2_2") (pintype "passive"))
      (node (ref "R48") (pin "2") (pinfunction "2_2") (pintype "passive"))
      (node (ref "R50") (pin "2") (pinfunction "2_2") (pintype "passive"))
      (node (ref "R52") (pin "2") (pinfunction "2_2") (pintype "passive"))
      (node (ref "R54") (pin "2") (pinfunction "2_2") (pintype "passive"))
      (node (ref "R56") (pin "2") (pinfunction "2_2") (pintype "passive"))
      (node (ref "R58") (pin "2") (pinfunction "2_2") (pintype "passive"))
      (node (ref "R6") (pin "2") (pinfunction "2_2") (pintype "passive"))
      (node (ref "R60") (pin "2") (pinfunction "2_2") (pintype "passive"))
      (node (ref "R62") (pin "2") (pinfunction "2_2") (pintype "passive"))
      (node (ref "R8") (pin "2") (pinfunction "2_2") (pintype "passive"))
      (node (ref "S1") (pin "1") (pinfunction "1_1") (pintype "passive"))
      (node (ref "U1") (pin "23") (pinfunction "VSS_23") (pintype "power_in"))
      (node (ref "U1") (pin "35") (pinfunction "VSS_35") (pintype "power_in"))
      (node (ref "U1") (pin "47") (pinfunction "VSS_47") (pintype "power_in"))
      (node (ref "U1") (pin "8") (pinfunction "VSSA_8") (pintype "power_in"))
      (node (ref "Y1") (pin "2") (pinfunction "GND_2") (pintype "power_in"))
      (node (ref "Y1") (pin "4") (pinfunction "GND_4") (pintype "power_in"))
    )
    (net (code "41") (name "Net-(U1-PD1_OSC_OUT)") (class "Default")
      (node (ref "R1") (pin "1") (pinfunction "1_1") (pintype "passive"))
      (node (ref "U1") (pin "6") (pinfunction "PD1_OSC_OUT_6") (pintype "bidirectional"))
    )
    (net (code "42") (name "unconnected-(U1-PC13-TAMPER-RTC-Pad2)") (class "Default")
      (node (ref "U1") (pin "2") (pinfunction "PC13-TAMPER-RTC_2") (pintype "bidirectional"))
    )
    (net (code "43") (name "unconnected-(U1-VBAT-Pad1)") (class "Default")
      (node (ref "U1") (pin "1") (pinfunction "VBAT_1") (pintype "bidirectional"))
    )
  )
)
